# CC3135_WIFI.net
KiCad netlist of a schematic drawn in Altium Designer
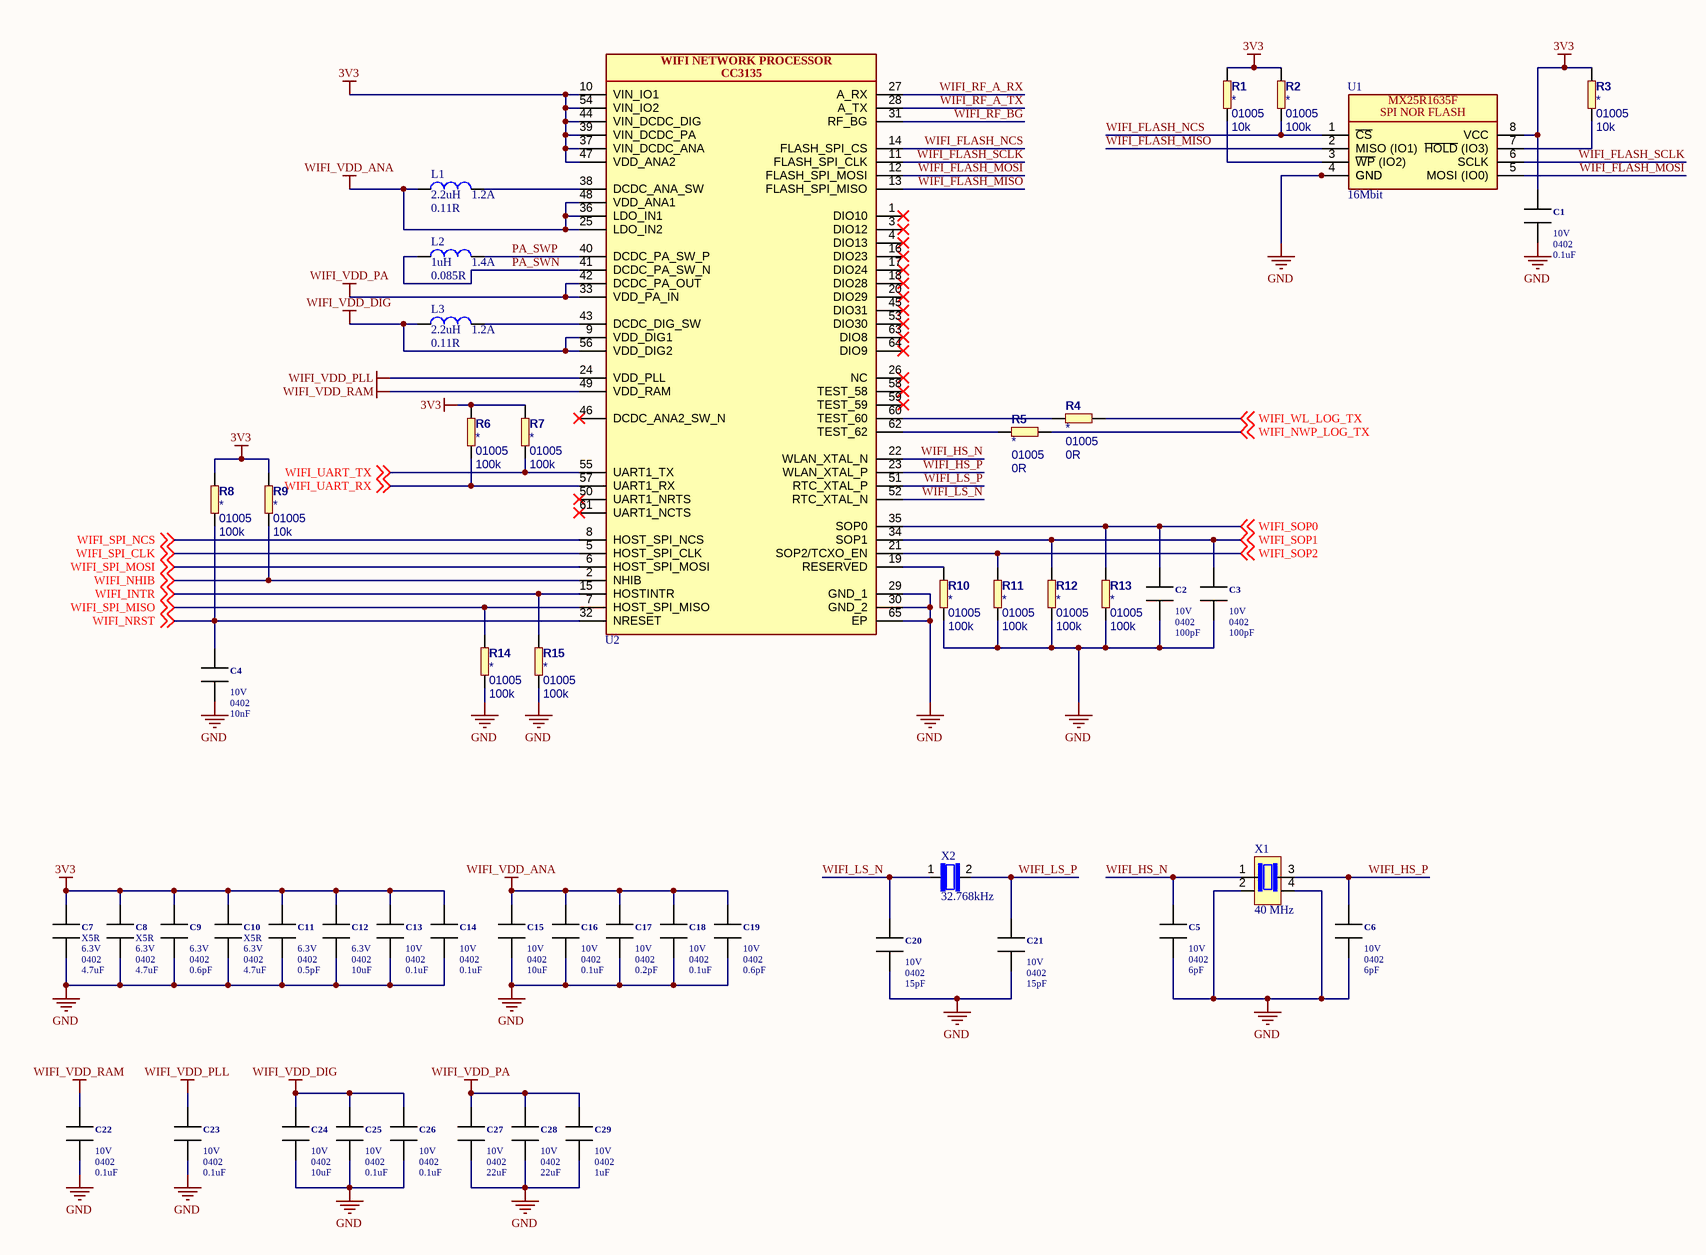
[diagram p0: CC3135_WIFI.SchDoc]

(export (version "E")
  (design (tool "Eeschema 10.0.6"))
  (components
    (comp (ref "C1")
      (value "MLCC_0402_(1005)")
      (footprint "MLCC_0402_(1005)")
      (fields
        (field (name "VOLTAGE") "10V")
        (field (name "PACKAGE") "0402")
        (field (name "CAPACITANCE") "0.1uF")
      )
      (libsource (lib "Capacitor_Ceramic") (part "MLCC_0402_(1005)"))
    )
    (comp (ref "C2")
      (value "MLCC_0402_(1005)")
      (footprint "MLCC_0402_(1005)")
      (fields
        (field (name "VOLTAGE") "10V")
        (field (name "PACKAGE") "0402")
        (field (name "CAPACITANCE") "100pF")
      )
      (libsource (lib "Capacitor_Ceramic") (part "MLCC_0402_(1005)"))
    )
    (comp (ref "C3")
      (value "MLCC_0402_(1005)")
      (footprint "MLCC_0402_(1005)")
      (fields
        (field (name "VOLTAGE") "10V")
        (field (name "PACKAGE") "0402")
        (field (name "CAPACITANCE") "100pF")
      )
      (libsource (lib "Capacitor_Ceramic") (part "MLCC_0402_(1005)"))
    )
    (comp (ref "C4")
      (value "MLCC_0402_(1005)")
      (footprint "MLCC_0402_(1005)")
      (fields
        (field (name "VOLTAGE") "10V")
        (field (name "PACKAGE") "0402")
        (field (name "CAPACITANCE") "10nF")
      )
      (libsource (lib "Capacitor_Ceramic") (part "MLCC_0402_(1005)"))
    )
    (comp (ref "C5")
      (value "MLCC_0402_(1005)")
      (footprint "MLCC_0402_(1005)")
      (fields
        (field (name "VOLTAGE") "10V")
        (field (name "PACKAGE") "0402")
        (field (name "CAPACITANCE") "6pF")
      )
      (libsource (lib "Capacitor_Ceramic") (part "MLCC_0402_(1005)"))
    )
    (comp (ref "C6")
      (value "MLCC_0402_(1005)")
      (footprint "MLCC_0402_(1005)")
      (fields
        (field (name "VOLTAGE") "10V")
        (field (name "PACKAGE") "0402")
        (field (name "CAPACITANCE") "6pF")
      )
      (libsource (lib "Capacitor_Ceramic") (part "MLCC_0402_(1005)"))
    )
    (comp (ref "C7")
      (value "MLCC_0402_(1005)")
      (footprint "MLCC_0402_(1005)")
      (fields
        (field (name "DIELECTRIC") "X5R")
        (field (name "VOLTAGE") "6.3V")
        (field (name "PACKAGE") "0402")
        (field (name "CAPACITANCE") "4.7uF")
      )
      (libsource (lib "Capacitor_Ceramic") (part "MLCC_0402_(1005)"))
    )
    (comp (ref "C8")
      (value "MLCC_0402_(1005)")
      (footprint "MLCC_0402_(1005)")
      (fields
        (field (name "DIELECTRIC") "X5R")
        (field (name "VOLTAGE") "6.3V")
        (field (name "PACKAGE") "0402")
        (field (name "CAPACITANCE") "4.7uF")
      )
      (libsource (lib "Capacitor_Ceramic") (part "MLCC_0402_(1005)"))
    )
    (comp (ref "C9")
      (value "MLCC_0402_(1005)")
      (footprint "MLCC_0402_(1005)")
      (fields
        (field (name "VOLTAGE") "6.3V")
        (field (name "PACKAGE") "0402")
        (field (name "CAPACITANCE") "0.6pF")
      )
      (libsource (lib "Capacitor_Ceramic") (part "MLCC_0402_(1005)"))
    )
    (comp (ref "C10")
      (value "MLCC_0402_(1005)")
      (footprint "MLCC_0402_(1005)")
      (fields
        (field (name "DIELECTRIC") "X5R")
        (field (name "VOLTAGE") "6.3V")
        (field (name "PACKAGE") "0402")
        (field (name "CAPACITANCE") "4.7uF")
      )
      (libsource (lib "Capacitor_Ceramic") (part "MLCC_0402_(1005)"))
    )
    (comp (ref "C11")
      (value "MLCC_0402_(1005)")
      (footprint "MLCC_0402_(1005)")
      (fields
        (field (name "VOLTAGE") "6.3V")
        (field (name "PACKAGE") "0402")
        (field (name "CAPACITANCE") "0.5pF")
      )
      (libsource (lib "Capacitor_Ceramic") (part "MLCC_0402_(1005)"))
    )
    (comp (ref "C12")
      (value "MLCC_0402_(1005)")
      (footprint "MLCC_0402_(1005)")
      (fields
        (field (name "VOLTAGE") "6.3V")
        (field (name "PACKAGE") "0402")
        (field (name "CAPACITANCE") "10uF")
      )
      (libsource (lib "Capacitor_Ceramic") (part "MLCC_0402_(1005)"))
    )
    (comp (ref "C13")
      (value "MLCC_0402_(1005)")
      (footprint "MLCC_0402_(1005)")
      (fields
        (field (name "VOLTAGE") "10V")
        (field (name "PACKAGE") "0402")
        (field (name "CAPACITANCE") "0.1uF")
      )
      (libsource (lib "Capacitor_Ceramic") (part "MLCC_0402_(1005)"))
    )
    (comp (ref "C14")
      (value "MLCC_0402_(1005)")
      (footprint "MLCC_0402_(1005)")
      (fields
        (field (name "VOLTAGE") "10V")
        (field (name "PACKAGE") "0402")
        (field (name "CAPACITANCE") "0.1uF")
      )
      (libsource (lib "Capacitor_Ceramic") (part "MLCC_0402_(1005)"))
    )
    (comp (ref "C15")
      (value "MLCC_0402_(1005)")
      (footprint "MLCC_0402_(1005)")
      (fields
        (field (name "VOLTAGE") "10V")
        (field (name "PACKAGE") "0402")
        (field (name "CAPACITANCE") "10uF")
      )
      (libsource (lib "Capacitor_Ceramic") (part "MLCC_0402_(1005)"))
    )
    (comp (ref "C16")
      (value "MLCC_0402_(1005)")
      (footprint "MLCC_0402_(1005)")
      (fields
        (field (name "VOLTAGE") "10V")
        (field (name "PACKAGE") "0402")
        (field (name "CAPACITANCE") "0.1uF")
      )
      (libsource (lib "Capacitor_Ceramic") (part "MLCC_0402_(1005)"))
    )
    (comp (ref "C17")
      (value "MLCC_0402_(1005)")
      (footprint "MLCC_0402_(1005)")
      (fields
        (field (name "VOLTAGE") "10V")
        (field (name "PACKAGE") "0402")
        (field (name "CAPACITANCE") "0.2pF")
      )
      (libsource (lib "Capacitor_Ceramic") (part "MLCC_0402_(1005)"))
    )
    (comp (ref "C18")
      (value "MLCC_0402_(1005)")
      (footprint "MLCC_0402_(1005)")
      (fields
        (field (name "VOLTAGE") "10V")
        (field (name "PACKAGE") "0402")
        (field (name "CAPACITANCE") "0.1uF")
      )
      (libsource (lib "Capacitor_Ceramic") (part "MLCC_0402_(1005)"))
    )
    (comp (ref "C19")
      (value "MLCC_0402_(1005)")
      (footprint "MLCC_0402_(1005)")
      (fields
        (field (name "VOLTAGE") "10V")
        (field (name "PACKAGE") "0402")
        (field (name "CAPACITANCE") "0.6pF")
      )
      (libsource (lib "Capacitor_Ceramic") (part "MLCC_0402_(1005)"))
    )
    (comp (ref "C20")
      (value "MLCC_0402_(1005)")
      (footprint "MLCC_0402_(1005)")
      (fields
        (field (name "VOLTAGE") "10V")
        (field (name "PACKAGE") "0402")
        (field (name "CAPACITANCE") "15pF")
      )
      (libsource (lib "Capacitor_Ceramic") (part "MLCC_0402_(1005)"))
    )
    (comp (ref "C21")
      (value "MLCC_0402_(1005)")
      (footprint "MLCC_0402_(1005)")
      (fields
        (field (name "VOLTAGE") "10V")
        (field (name "PACKAGE") "0402")
        (field (name "CAPACITANCE") "15pF")
      )
      (libsource (lib "Capacitor_Ceramic") (part "MLCC_0402_(1005)"))
    )
    (comp (ref "C22")
      (value "MLCC_0402_(1005)")
      (footprint "MLCC_0402_(1005)")
      (fields
        (field (name "VOLTAGE") "10V")
        (field (name "PACKAGE") "0402")
        (field (name "CAPACITANCE") "0.1uF")
      )
      (libsource (lib "Capacitor_Ceramic") (part "MLCC_0402_(1005)"))
    )
    (comp (ref "C23")
      (value "MLCC_0402_(1005)")
      (footprint "MLCC_0402_(1005)")
      (fields
        (field (name "VOLTAGE") "10V")
        (field (name "PACKAGE") "0402")
        (field (name "CAPACITANCE") "0.1uF")
      )
      (libsource (lib "Capacitor_Ceramic") (part "MLCC_0402_(1005)"))
    )
    (comp (ref "C24")
      (value "MLCC_0402_(1005)")
      (footprint "MLCC_0402_(1005)")
      (fields
        (field (name "VOLTAGE") "10V")
        (field (name "PACKAGE") "0402")
        (field (name "CAPACITANCE") "10uF")
      )
      (libsource (lib "Capacitor_Ceramic") (part "MLCC_0402_(1005)"))
    )
    (comp (ref "C25")
      (value "MLCC_0402_(1005)")
      (footprint "MLCC_0402_(1005)")
      (fields
        (field (name "VOLTAGE") "10V")
        (field (name "PACKAGE") "0402")
        (field (name "CAPACITANCE") "0.1uF")
      )
      (libsource (lib "Capacitor_Ceramic") (part "MLCC_0402_(1005)"))
    )
    (comp (ref "C26")
      (value "MLCC_0402_(1005)")
      (footprint "MLCC_0402_(1005)")
      (fields
        (field (name "VOLTAGE") "10V")
        (field (name "PACKAGE") "0402")
        (field (name "CAPACITANCE") "0.1uF")
      )
      (libsource (lib "Capacitor_Ceramic") (part "MLCC_0402_(1005)"))
    )
    (comp (ref "C27")
      (value "MLCC_0402_(1005)")
      (footprint "MLCC_0402_(1005)")
      (fields
        (field (name "VOLTAGE") "10V")
        (field (name "PACKAGE") "0402")
        (field (name "CAPACITANCE") "22uF")
      )
      (libsource (lib "Capacitor_Ceramic") (part "MLCC_0402_(1005)"))
    )
    (comp (ref "C28")
      (value "MLCC_0402_(1005)")
      (footprint "MLCC_0402_(1005)")
      (fields
        (field (name "VOLTAGE") "10V")
        (field (name "PACKAGE") "0402")
        (field (name "CAPACITANCE") "22uF")
      )
      (libsource (lib "Capacitor_Ceramic") (part "MLCC_0402_(1005)"))
    )
    (comp (ref "C29")
      (value "MLCC_0402_(1005)")
      (footprint "MLCC_0402_(1005)")
      (fields
        (field (name "VOLTAGE") "10V")
        (field (name "PACKAGE") "0402")
        (field (name "CAPACITANCE") "1uF")
      )
      (libsource (lib "Capacitor_Ceramic") (part "MLCC_0402_(1005)"))
    )
    (comp (ref "L1")
      (value "2.2uH")
      (footprint "LQM2MPN")
      (description "1.2A 138mΩ 2.2uH 40MHz ±20% 0806 Inductors (SMD) ROHS")
      (fields (field (name "DCR") "0.11R") (field (name "ISAT") "1.2A") (field (name "Comment") "LQM2MPN"))
      (libsource (lib "Inductor") (part "LQM2MPN"))
    )
    (comp (ref "L2")
      (value "1uH")
      (footprint "LQM2MPN")
      (description "1.2A 138mΩ 2.2uH 40MHz ±20% 0806 Inductors (SMD) ROHS")
      (fields (field (name "DCR") "0.085R") (field (name "ISAT") "1.4A") (field (name "Comment") "LQM2MPN"))
      (libsource (lib "Inductor") (part "LQM2MPN"))
    )
    (comp (ref "L3")
      (value "2.2uH")
      (footprint "LQM2MPN")
      (description "1.2A 138mΩ 2.2uH 40MHz ±20% 0806 Inductors (SMD) ROHS")
      (fields (field (name "DCR") "0.11R") (field (name "ISAT") "1.2A") (field (name "Comment") "LQM2MPN"))
      (libsource (lib "Inductor") (part "LQM2MPN"))
    )
    (comp (ref "R1")
      (value "RES_01005_(0402)")
      (footprint "RES_01005_(0402)")
      (fields
        (field (name "TOLERANCE") "*")
        (field (name "PACKAGE") "01005")
        (field (name "RESISTANCE") "10k")
      )
      (libsource (lib "Resistor_Film") (part "RES_01005_(0402)"))
    )
    (comp (ref "R2")
      (value "RES_01005_(0402)")
      (footprint "RES_01005_(0402)")
      (fields
        (field (name "TOLERANCE") "*")
        (field (name "PACKAGE") "01005")
        (field (name "RESISTANCE") "100k")
      )
      (libsource (lib "") (part "RES_01005_(0402)_1"))
    )
    (comp (ref "R3")
      (value "RES_01005_(0402)")
      (footprint "RES_01005_(0402)")
      (fields
        (field (name "TOLERANCE") "*")
        (field (name "PACKAGE") "01005")
        (field (name "RESISTANCE") "10k")
      )
      (libsource (lib "Resistor_Film") (part "RES_01005_(0402)"))
    )
    (comp (ref "R4")
      (value "RES_01005_(0402)")
      (footprint "RES_01005_(0402)")
      (fields
        (field (name "TOLERANCE") "*")
        (field (name "PACKAGE") "01005")
        (field (name "RESISTANCE") "0R")
      )
      (libsource (lib "") (part "RES_01005_(0402)_2"))
    )
    (comp (ref "R5")
      (value "RES_01005_(0402)")
      (footprint "RES_01005_(0402)")
      (fields
        (field (name "TOLERANCE") "*")
        (field (name "PACKAGE") "01005")
        (field (name "RESISTANCE") "0R")
      )
      (libsource (lib "") (part "RES_01005_(0402)_2"))
    )
    (comp (ref "R6")
      (value "RES_01005_(0402)")
      (footprint "RES_01005_(0402)")
      (fields
        (field (name "TOLERANCE") "*")
        (field (name "PACKAGE") "01005")
        (field (name "RESISTANCE") "100k")
      )
      (libsource (lib "") (part "RES_01005_(0402)_1"))
    )
    (comp (ref "R7")
      (value "RES_01005_(0402)")
      (footprint "RES_01005_(0402)")
      (fields
        (field (name "TOLERANCE") "*")
        (field (name "PACKAGE") "01005")
        (field (name "RESISTANCE") "100k")
      )
      (libsource (lib "") (part "RES_01005_(0402)_1"))
    )
    (comp (ref "R8")
      (value "RES_01005_(0402)")
      (footprint "RES_01005_(0402)")
      (fields
        (field (name "TOLERANCE") "*")
        (field (name "PACKAGE") "01005")
        (field (name "RESISTANCE") "100k")
      )
      (libsource (lib "") (part "RES_01005_(0402)_1"))
    )
    (comp (ref "R9")
      (value "RES_01005_(0402)")
      (footprint "RES_01005_(0402)")
      (fields
        (field (name "TOLERANCE") "*")
        (field (name "PACKAGE") "01005")
        (field (name "RESISTANCE") "10k")
      )
      (libsource (lib "") (part "RES_01005_(0402)_1"))
    )
    (comp (ref "R10")
      (value "RES_01005_(0402)")
      (footprint "RES_01005_(0402)")
      (fields
        (field (name "TOLERANCE") "*")
        (field (name "PACKAGE") "01005")
        (field (name "RESISTANCE") "100k")
      )
      (libsource (lib "") (part "RES_01005_(0402)_1"))
    )
    (comp (ref "R11")
      (value "RES_01005_(0402)")
      (footprint "RES_01005_(0402)")
      (fields
        (field (name "TOLERANCE") "*")
        (field (name "PACKAGE") "01005")
        (field (name "RESISTANCE") "100k")
      )
      (libsource (lib "") (part "RES_01005_(0402)_1"))
    )
    (comp (ref "R12")
      (value "RES_01005_(0402)")
      (footprint "RES_01005_(0402)")
      (fields
        (field (name "TOLERANCE") "*")
        (field (name "PACKAGE") "01005")
        (field (name "RESISTANCE") "100k")
      )
      (libsource (lib "") (part "RES_01005_(0402)_1"))
    )
    (comp (ref "R13")
      (value "RES_01005_(0402)")
      (footprint "RES_01005_(0402)")
      (fields
        (field (name "TOLERANCE") "*")
        (field (name "PACKAGE") "01005")
        (field (name "RESISTANCE") "100k")
      )
      (libsource (lib "") (part "RES_01005_(0402)_1"))
    )
    (comp (ref "R14")
      (value "RES_01005_(0402)")
      (footprint "RES_01005_(0402)")
      (fields
        (field (name "TOLERANCE") "*")
        (field (name "PACKAGE") "01005")
        (field (name "RESISTANCE") "100k")
      )
      (libsource (lib "") (part "RES_01005_(0402)_1"))
    )
    (comp (ref "R15")
      (value "RES_01005_(0402)")
      (footprint "RES_01005_(0402)")
      (fields
        (field (name "TOLERANCE") "*")
        (field (name "PACKAGE") "01005")
        (field (name "RESISTANCE") "100k")
      )
      (libsource (lib "") (part "RES_01005_(0402)_1"))
    )
    (comp (ref "U1")
      (value "16Mbit")
      (footprint "MX25R1635FZU")
      (description "1.65V~3.6V 100,000 Cycles 16Mbit 20 Years 3.2ms 80MHz SPI NOR FLASH ROHS")
      (fields (field (name "Comment") "MX25R1635F"))
      (libsource (lib "FLASH") (part "MX25R1635F"))
    )
    (comp (ref "U2")
      (value "CC3135RNMRGKR")
      (footprint "QFN50P900X900X100-65N-D")
      (libsource (lib "RF_Transceiver") (part "CC3135RNMRGKR"))
    )
    (comp (ref "X1")
      (value "ABM13W")
      (footprint "ABM13W")
      (description "ABM13W Package")
      (fields (field (name "FREQUENCY") "40 MHz"))
      (libsource (lib "Crystal") (part "ABM13W"))
    )
    (comp (ref "X2")
      (value "ECX-1210")
      (footprint "ECX-1210")
      (description "ECX 1210 Package")
      (fields (field (name "FREQUENCY") "32.768kHz"))
      (libsource (lib "Crystal") (part "ECX-1210"))
    )
  )
  (nets
    (net (code "1") (name "/PA_SWN") (class "Default")
      (node (ref "L2") (pin "1") (pinfunction "1_1") (pintype "passive"))
      (node (ref "U2") (pin "41") (pinfunction "DCDC_PA_SW_N_41") (pintype "passive"))
    )
    (net (code "2") (name "/PA_SWP") (class "Default")
      (node (ref "L2") (pin "2") (pinfunction "2_2") (pintype "passive"))
      (node (ref "U2") (pin "40") (pinfunction "DCDC_PA_SW_P_40") (pintype "passive"))
    )
    (net (code "3") (name "/WIFI_FLASH_MISO") (class "Default")
      (node (ref "U1") (pin "2") (pinfunction "MISO_(IO1)_2") (pintype "passive"))
      (node (ref "U2") (pin "13") (pinfunction "FLASH_SPI_MISO_13") (pintype "passive"))
    )
    (net (code "4") (name "/WIFI_FLASH_MOSI") (class "Default")
      (node (ref "U1") (pin "5") (pinfunction "MOSI_(IO0)_5") (pintype "passive"))
      (node (ref "U2") (pin "12") (pinfunction "FLASH_SPI_MOSI_12") (pintype "passive"))
    )
    (net (code "5") (name "/WIFI_FLASH_NCS") (class "Default")
      (node (ref "R2") (pin "2") (pinfunction "2_2") (pintype "passive"))
      (node (ref "U1") (pin "1") (pinfunction "~{CS}_1") (pintype "passive"))
      (node (ref "U2") (pin "14") (pinfunction "FLASH_SPI_CS_14") (pintype "passive"))
    )
    (net (code "6") (name "/WIFI_FLASH_SCLK") (class "Default")
      (node (ref "U1") (pin "6") (pinfunction "SCLK_6") (pintype "passive"))
      (node (ref "U2") (pin "11") (pinfunction "FLASH_SPI_CLK_11") (pintype "passive"))
    )
    (net (code "7") (name "/WIFI_HS_N") (class "Default")
      (node (ref "C5") (pin "1") (pinfunction "1_1") (pintype "passive"))
      (node (ref "U2") (pin "22") (pinfunction "WLAN_XTAL_N_22") (pintype "passive"))
      (node (ref "X1") (pin "1") (pinfunction "1_1") (pintype "passive"))
    )
    (net (code "8") (name "/WIFI_HS_P") (class "Default")
      (node (ref "C6") (pin "1") (pinfunction "1_1") (pintype "passive"))
      (node (ref "U2") (pin "23") (pinfunction "WLAN_XTAL_P_23") (pintype "passive"))
      (node (ref "X1") (pin "3") (pinfunction "3_3") (pintype "passive"))
    )
    (net (code "9") (name "/WIFI_LS_N") (class "Default")
      (node (ref "C20") (pin "1") (pinfunction "1_1") (pintype "passive"))
      (node (ref "U2") (pin "52") (pinfunction "RTC_XTAL_N_52") (pintype "passive"))
      (node (ref "X2") (pin "1") (pinfunction "1_1") (pintype "passive"))
    )
    (net (code "10") (name "/WIFI_LS_P") (class "Default")
      (node (ref "C21") (pin "1") (pinfunction "1_1") (pintype "passive"))
      (node (ref "U2") (pin "51") (pinfunction "RTC_XTAL_P_51") (pintype "passive"))
      (node (ref "X2") (pin "2") (pinfunction "2_2") (pintype "passive"))
    )
    (net (code "11") (name "/WIFI_RF_A_RX") (class "Default")
      (node (ref "U2") (pin "27") (pinfunction "A_RX_27") (pintype "passive"))
    )
    (net (code "12") (name "/WIFI_RF_A_TX") (class "Default")
      (node (ref "U2") (pin "28") (pinfunction "A_TX_28") (pintype "passive"))
    )
    (net (code "13") (name "/WIFI_RF_BG") (class "Default")
      (node (ref "U2") (pin "31") (pinfunction "RF_BG_31") (pintype "passive"))
    )
    (net (code "14") (name "3V3") (class "Default")
      (node (ref "C1") (pin "1") (pinfunction "1_1") (pintype "passive"))
      (node (ref "C10") (pin "1") (pinfunction "1_1") (pintype "passive"))
      (node (ref "C11") (pin "1") (pinfunction "1_1") (pintype "passive"))
      (node (ref "C12") (pin "1") (pinfunction "1_1") (pintype "passive"))
      (node (ref "C13") (pin "1") (pinfunction "1_1") (pintype "passive"))
      (node (ref "C14") (pin "1") (pinfunction "1_1") (pintype "passive"))
      (node (ref "C7") (pin "1") (pinfunction "1_1") (pintype "passive"))
      (node (ref "C8") (pin "1") (pinfunction "1_1") (pintype "passive"))
      (node (ref "C9") (pin "1") (pinfunction "1_1") (pintype "passive"))
      (node (ref "R1") (pin "2") (pinfunction "2_2") (pintype "passive"))
      (node (ref "R2") (pin "1") (pinfunction "1_1") (pintype "passive"))
      (node (ref "R3") (pin "2") (pinfunction "2_2") (pintype "passive"))
      (node (ref "R6") (pin "1") (pinfunction "1_1") (pintype "passive"))
      (node (ref "R7") (pin "1") (pinfunction "1_1") (pintype "passive"))
      (node (ref "R8") (pin "1") (pinfunction "1_1") (pintype "passive"))
      (node (ref "R9") (pin "1") (pinfunction "1_1") (pintype "passive"))
      (node (ref "U1") (pin "8") (pinfunction "VCC_8") (pintype "passive"))
      (node (ref "U2") (pin "10") (pinfunction "VIN_IO1_10") (pintype "passive"))
      (node (ref "U2") (pin "37") (pinfunction "VIN_DCDC_ANA_37") (pintype "passive"))
      (node (ref "U2") (pin "39") (pinfunction "VIN_DCDC_PA_39") (pintype "passive"))
      (node (ref "U2") (pin "44") (pinfunction "VIN_DCDC_DIG_44") (pintype "passive"))
      (node (ref "U2") (pin "47") (pinfunction "VDD_ANA2_47") (pintype "passive"))
      (node (ref "U2") (pin "54") (pinfunction "VIN_IO2_54") (pintype "passive"))
    )
    (net (code "15") (name "GND") (class "Default")
      (node (ref "C1") (pin "2") (pinfunction "2_2") (pintype "passive"))
      (node (ref "C10") (pin "2") (pinfunction "2_2") (pintype "passive"))
      (node (ref "C11") (pin "2") (pinfunction "2_2") (pintype "passive"))
      (node (ref "C12") (pin "2") (pinfunction "2_2") (pintype "passive"))
      (node (ref "C13") (pin "2") (pinfunction "2_2") (pintype "passive"))
      (node (ref "C14") (pin "2") (pinfunction "2_2") (pintype "passive"))
      (node (ref "C15") (pin "2") (pinfunction "2_2") (pintype "passive"))
      (node (ref "C16") (pin "2") (pinfunction "2_2") (pintype "passive"))
      (node (ref "C17") (pin "2") (pinfunction "2_2") (pintype "passive"))
      (node (ref "C18") (pin "2") (pinfunction "2_2") (pintype "passive"))
      (node (ref "C19") (pin "2") (pinfunction "2_2") (pintype "passive"))
      (node (ref "C2") (pin "2") (pinfunction "2_2") (pintype "passive"))
      (node (ref "C20") (pin "2") (pinfunction "2_2") (pintype "passive"))
      (node (ref "C21") (pin "2") (pinfunction "2_2") (pintype "passive"))
      (node (ref "C22") (pin "2") (pinfunction "2_2") (pintype "passive"))
      (node (ref "C23") (pin "2") (pinfunction "2_2") (pintype "passive"))
      (node (ref "C24") (pin "2") (pinfunction "2_2") (pintype "passive"))
      (node (ref "C25") (pin "2") (pinfunction "2_2") (pintype "passive"))
      (node (ref "C26") (pin "2") (pinfunction "2_2") (pintype "passive"))
      (node (ref "C27") (pin "2") (pinfunction "2_2") (pintype "passive"))
      (node (ref "C28") (pin "2") (pinfunction "2_2") (pintype "passive"))
      (node (ref "C29") (pin "2") (pinfunction "2_2") (pintype "passive"))
      (node (ref "C3") (pin "2") (pinfunction "2_2") (pintype "passive"))
      (node (ref "C4") (pin "2") (pinfunction "2_2") (pintype "passive"))
      (node (ref "C5") (pin "2") (pinfunction "2_2") (pintype "passive"))
      (node (ref "C6") (pin "2") (pinfunction "2_2") (pintype "passive"))
      (node (ref "C7") (pin "2") (pinfunction "2_2") (pintype "passive"))
      (node (ref "C8") (pin "2") (pinfunction "2_2") (pintype "passive"))
      (node (ref "C9") (pin "2") (pinfunction "2_2") (pintype "passive"))
      (node (ref "R10") (pin "2") (pinfunction "2_2") (pintype "passive"))
      (node (ref "R11") (pin "2") (pinfunction "2_2") (pintype "passive"))
      (node (ref "R12") (pin "2") (pinfunction "2_2") (pintype "passive"))
      (node (ref "R13") (pin "2") (pinfunction "2_2") (pintype "passive"))
      (node (ref "R14") (pin "2") (pinfunction "2_2") (pintype "passive"))
      (node (ref "R15") (pin "2") (pinfunction "2_2") (pintype "passive"))
      (node (ref "U1") (pin "4") (pinfunction "GND_4") (pintype "passive"))
      (node (ref "U1") (pin "9") (pinfunction "GND_9") (pintype "passive"))
      (node (ref "U2") (pin "29") (pinfunction "GND_1_29") (pintype "passive"))
      (node (ref "U2") (pin "30") (pinfunction "GND_2_30") (pintype "passive"))
      (node (ref "U2") (pin "65") (pinfunction "EP_65") (pintype "passive"))
      (node (ref "X1") (pin "2") (pinfunction "2_2") (pintype "passive"))
      (node (ref "X1") (pin "4") (pinfunction "4_4") (pintype "passive"))
    )
    (net (code "16") (name "Net-(U1-~{HOLD}_(IO3))") (class "Default")
      (node (ref "R3") (pin "1") (pinfunction "1_1") (pintype "passive"))
      (node (ref "U1") (pin "7") (pinfunction "~{HOLD}_(IO3)_7") (pintype "passive"))
    )
    (net (code "17") (name "Net-(U1-~{WP}_(IO2))") (class "Default")
      (node (ref "R1") (pin "1") (pinfunction "1_1") (pintype "passive"))
      (node (ref "U1") (pin "3") (pinfunction "~{WP}_(IO2)_3") (pintype "passive"))
    )
    (net (code "18") (name "Net-(U2-DCDC_ANA_SW)") (class "Default")
      (node (ref "L1") (pin "2") (pinfunction "2_2") (pintype "passive"))
      (node (ref "U2") (pin "38") (pinfunction "DCDC_ANA_SW_38") (pintype "passive"))
    )
    (net (code "19") (name "Net-(U2-DCDC_DIG_SW)") (class "Default")
      (node (ref "L3") (pin "2") (pinfunction "2_2") (pintype "passive"))
      (node (ref "U2") (pin "43") (pinfunction "DCDC_DIG_SW_43") (pintype "passive"))
    )
    (net (code "20") (name "Net-(U2-RESERVED)") (class "Default")
      (node (ref "R10") (pin "1") (pinfunction "1_1") (pintype "passive"))
      (node (ref "U2") (pin "19") (pinfunction "RESERVED_19") (pintype "passive"))
    )
    (net (code "21") (name "Net-(U2-TEST_60)") (class "Default")
      (node (ref "R4") (pin "1") (pinfunction "1_1") (pintype "passive"))
      (node (ref "U2") (pin "60") (pinfunction "TEST_60_60") (pintype "passive"))
    )
    (net (code "22") (name "Net-(U2-TEST_62)") (class "Default")
      (node (ref "R5") (pin "1") (pinfunction "1_1") (pintype "passive"))
      (node (ref "U2") (pin "62") (pinfunction "TEST_62_62") (pintype "passive"))
    )
    (net (code "23") (name "WIFI_INTR") (class "Default")
      (node (ref "R15") (pin "1") (pinfunction "1_1") (pintype "passive"))
      (node (ref "U2") (pin "15") (pinfunction "HOSTINTR_15") (pintype "passive"))
    )
    (net (code "24") (name "WIFI_NHIB") (class "Default")
      (node (ref "R9") (pin "2") (pinfunction "2_2") (pintype "passive"))
      (node (ref "U2") (pin "2") (pinfunction "NHIB_2") (pintype "passive"))
    )
    (net (code "25") (name "WIFI_NRST") (class "Default")
      (node (ref "C4") (pin "1") (pinfunction "1_1") (pintype "passive"))
      (node (ref "R8") (pin "2") (pinfunction "2_2") (pintype "passive"))
      (node (ref "U2") (pin "32") (pinfunction "NRESET_32") (pintype "passive"))
    )
    (net (code "26") (name "WIFI_NWP_LOG_TX") (class "Default")
      (node (ref "R5") (pin "2") (pinfunction "2_2") (pintype "passive"))
    )
    (net (code "27") (name "WIFI_SOP0") (class "Default")
      (node (ref "C2") (pin "1") (pinfunction "1_1") (pintype "passive"))
      (node (ref "R13") (pin "1") (pinfunction "1_1") (pintype "passive"))
      (node (ref "U2") (pin "35") (pinfunction "SOP0_35") (pintype "passive"))
    )
    (net (code "28") (name "WIFI_SOP1") (class "Default")
      (node (ref "C3") (pin "1") (pinfunction "1_1") (pintype "passive"))
      (node (ref "R12") (pin "1") (pinfunction "1_1") (pintype "passive"))
      (node (ref "U2") (pin "34") (pinfunction "SOP1_34") (pintype "passive"))
    )
    (net (code "29") (name "WIFI_SOP2") (class "Default")
      (node (ref "R11") (pin "1") (pinfunction "1_1") (pintype "passive"))
      (node (ref "U2") (pin "21") (pinfunction "SOP2/TCXO_EN_21") (pintype "passive"))
    )
    (net (code "30") (name "WIFI_SPI_CLK") (class "Default")
      (node (ref "U2") (pin "5") (pinfunction "HOST_SPI_CLK_5") (pintype "passive"))
    )
    (net (code "31") (name "WIFI_SPI_MISO") (class "Default")
      (node (ref "R14") (pin "1") (pinfunction "1_1") (pintype "passive"))
      (node (ref "U2") (pin "7") (pinfunction "HOST_SPI_MISO_7") (pintype "passive"))
    )
    (net (code "32") (name "WIFI_SPI_MOSI") (class "Default")
      (node (ref "U2") (pin "6") (pinfunction "HOST_SPI_MOSI_6") (pintype "passive"))
    )
    (net (code "33") (name "WIFI_SPI_NCS") (class "Default")
      (node (ref "U2") (pin "8") (pinfunction "HOST_SPI_NCS_8") (pintype "passive"))
    )
    (net (code "34") (name "WIFI_UART_RX") (class "Default")
      (node (ref "R6") (pin "2") (pinfunction "2_2") (pintype "passive"))
      (node (ref "U2") (pin "57") (pinfunction "UART1_RX_57") (pintype "passive"))
    )
    (net (code "35") (name "WIFI_UART_TX") (class "Default")
      (node (ref "R7") (pin "2") (pinfunction "2_2") (pintype "passive"))
      (node (ref "U2") (pin "55") (pinfunction "UART1_TX_55") (pintype "passive"))
    )
    (net (code "36") (name "WIFI_VDD_ANA") (class "Default")
      (node (ref "C15") (pin "1") (pinfunction "1_1") (pintype "passive"))
      (node (ref "C16") (pin "1") (pinfunction "1_1") (pintype "passive"))
      (node (ref "C17") (pin "1") (pinfunction "1_1") (pintype "passive"))
      (node (ref "C18") (pin "1") (pinfunction "1_1") (pintype "passive"))
      (node (ref "C19") (pin "1") (pinfunction "1_1") (pintype "passive"))
      (node (ref "L1") (pin "1") (pinfunction "1_1") (pintype "passive"))
      (node (ref "U2") (pin "25") (pinfunction "LDO_IN2_25") (pintype "passive"))
      (node (ref "U2") (pin "36") (pinfunction "LDO_IN1_36") (pintype "passive"))
      (node (ref "U2") (pin "48") (pinfunction "VDD_ANA1_48") (pintype "passive"))
    )
    (net (code "37") (name "WIFI_VDD_DIG") (class "Default")
      (node (ref "C24") (pin "1") (pinfunction "1_1") (pintype "passive"))
      (node (ref "C25") (pin "1") (pinfunction "1_1") (pintype "passive"))
      (node (ref "C26") (pin "1") (pinfunction "1_1") (pintype "passive"))
      (node (ref "L3") (pin "1") (pinfunction "1_1") (pintype "passive"))
      (node (ref "U2") (pin "56") (pinfunction "VDD_DIG2_56") (pintype "passive"))
      (node (ref "U2") (pin "9") (pinfunction "VDD_DIG1_9") (pintype "passive"))
    )
    (net (code "38") (name "WIFI_VDD_PA") (class "Default")
      (node (ref "C27") (pin "1") (pinfunction "1_1") (pintype "passive"))
      (node (ref "C28") (pin "1") (pinfunction "1_1") (pintype "passive"))
      (node (ref "C29") (pin "1") (pinfunction "1_1") (pintype "passive"))
      (node (ref "U2") (pin "33") (pinfunction "VDD_PA_IN_33") (pintype "passive"))
      (node (ref "U2") (pin "42") (pinfunction "DCDC_PA_OUT_42") (pintype "passive"))
    )
    (net (code "39") (name "WIFI_VDD_PLL") (class "Default")
      (node (ref "C23") (pin "1") (pinfunction "1_1") (pintype "passive"))
      (node (ref "U2") (pin "24") (pinfunction "VDD_PLL_24") (pintype "passive"))
    )
    (net (code "40") (name "WIFI_VDD_RAM") (class "Default")
      (node (ref "C22") (pin "1") (pinfunction "1_1") (pintype "passive"))
      (node (ref "U2") (pin "49") (pinfunction "VDD_RAM_49") (pintype "passive"))
    )
    (net (code "41") (name "WIFI_WL_LOG_TX") (class "Default")
      (node (ref "R4") (pin "2") (pinfunction "2_2") (pintype "passive"))
    )
    (net (code "42") (name "unconnected-(U2-DCDC_ANA2_SW_N-Pad46)") (class "Default")
      (node (ref "U2") (pin "46") (pinfunction "DCDC_ANA2_SW_N_46") (pintype "passive+no_connect"))
    )
    (net (code "43") (name "unconnected-(U2-DIO8-Pad63)") (class "Default")
      (node (ref "U2") (pin "63") (pinfunction "DIO8_63") (pintype "passive+no_connect"))
    )
    (net (code "44") (name "unconnected-(U2-DIO9-Pad64)") (class "Default")
      (node (ref "U2") (pin "64") (pinfunction "DIO9_64") (pintype "passive+no_connect"))
    )
    (net (code "45") (name "unconnected-(U2-DIO10-Pad1)") (class "Default")
      (node (ref "U2") (pin "1") (pinfunction "DIO10_1") (pintype "passive+no_connect"))
    )
    (net (code "46") (name "unconnected-(U2-DIO12-Pad3)") (class "Default")
      (node (ref "U2") (pin "3") (pinfunction "DIO12_3") (pintype "passive+no_connect"))
    )
    (net (code "47") (name "unconnected-(U2-DIO13-Pad4)") (class "Default")
      (node (ref "U2") (pin "4") (pinfunction "DIO13_4") (pintype "passive+no_connect"))
    )
    (net (code "48") (name "unconnected-(U2-DIO23-Pad16)") (class "Default")
      (node (ref "U2") (pin "16") (pinfunction "DIO23_16") (pintype "passive+no_connect"))
    )
    (net (code "49") (name "unconnected-(U2-DIO24-Pad17)") (class "Default")
      (node (ref "U2") (pin "17") (pinfunction "DIO24_17") (pintype "passive+no_connect"))
    )
    (net (code "50") (name "unconnected-(U2-DIO28-Pad18)") (class "Default")
      (node (ref "U2") (pin "18") (pinfunction "DIO28_18") (pintype "passive+no_connect"))
    )
    (net (code "51") (name "unconnected-(U2-DIO29-Pad20)") (class "Default")
      (node (ref "U2") (pin "20") (pinfunction "DIO29_20") (pintype "passive+no_connect"))
    )
    (net (code "52") (name "unconnected-(U2-DIO30-Pad53)") (class "Default")
      (node (ref "U2") (pin "53") (pinfunction "DIO30_53") (pintype "passive+no_connect"))
    )
    (net (code "53") (name "unconnected-(U2-DIO31-Pad45)") (class "Default")
      (node (ref "U2") (pin "45") (pinfunction "DIO31_45") (pintype "passive+no_connect"))
    )
    (net (code "54") (name "unconnected-(U2-NC-Pad26)") (class "Default")
      (node (ref "U2") (pin "26") (pinfunction "NC_26") (pintype "passive+no_connect"))
    )
    (net (code "55") (name "unconnected-(U2-TEST_58-Pad58)") (class "Default")
      (node (ref "U2") (pin "58") (pinfunction "TEST_58_58") (pintype "passive+no_connect"))
    )
    (net (code "56") (name "unconnected-(U2-TEST_59-Pad59)") (class "Default")
      (node (ref "U2") (pin "59") (pinfunction "TEST_59_59") (pintype "passive+no_connect"))
    )
    (net (code "57") (name "unconnected-(U2-UART1_NCTS-Pad61)") (class "Default")
      (node (ref "U2") (pin "61") (pinfunction "UART1_NCTS_61") (pintype "passive+no_connect"))
    )
    (net (code "58") (name "unconnected-(U2-UART1_NRTS-Pad50)") (class "Default")
      (node (ref "U2") (pin "50") (pinfunction "UART1_NRTS_50") (pintype "passive+no_connect"))
    )
  )
)
